# FiltrosRF_R00.net
KiCad netlist of a schematic drawn in Altium Designer
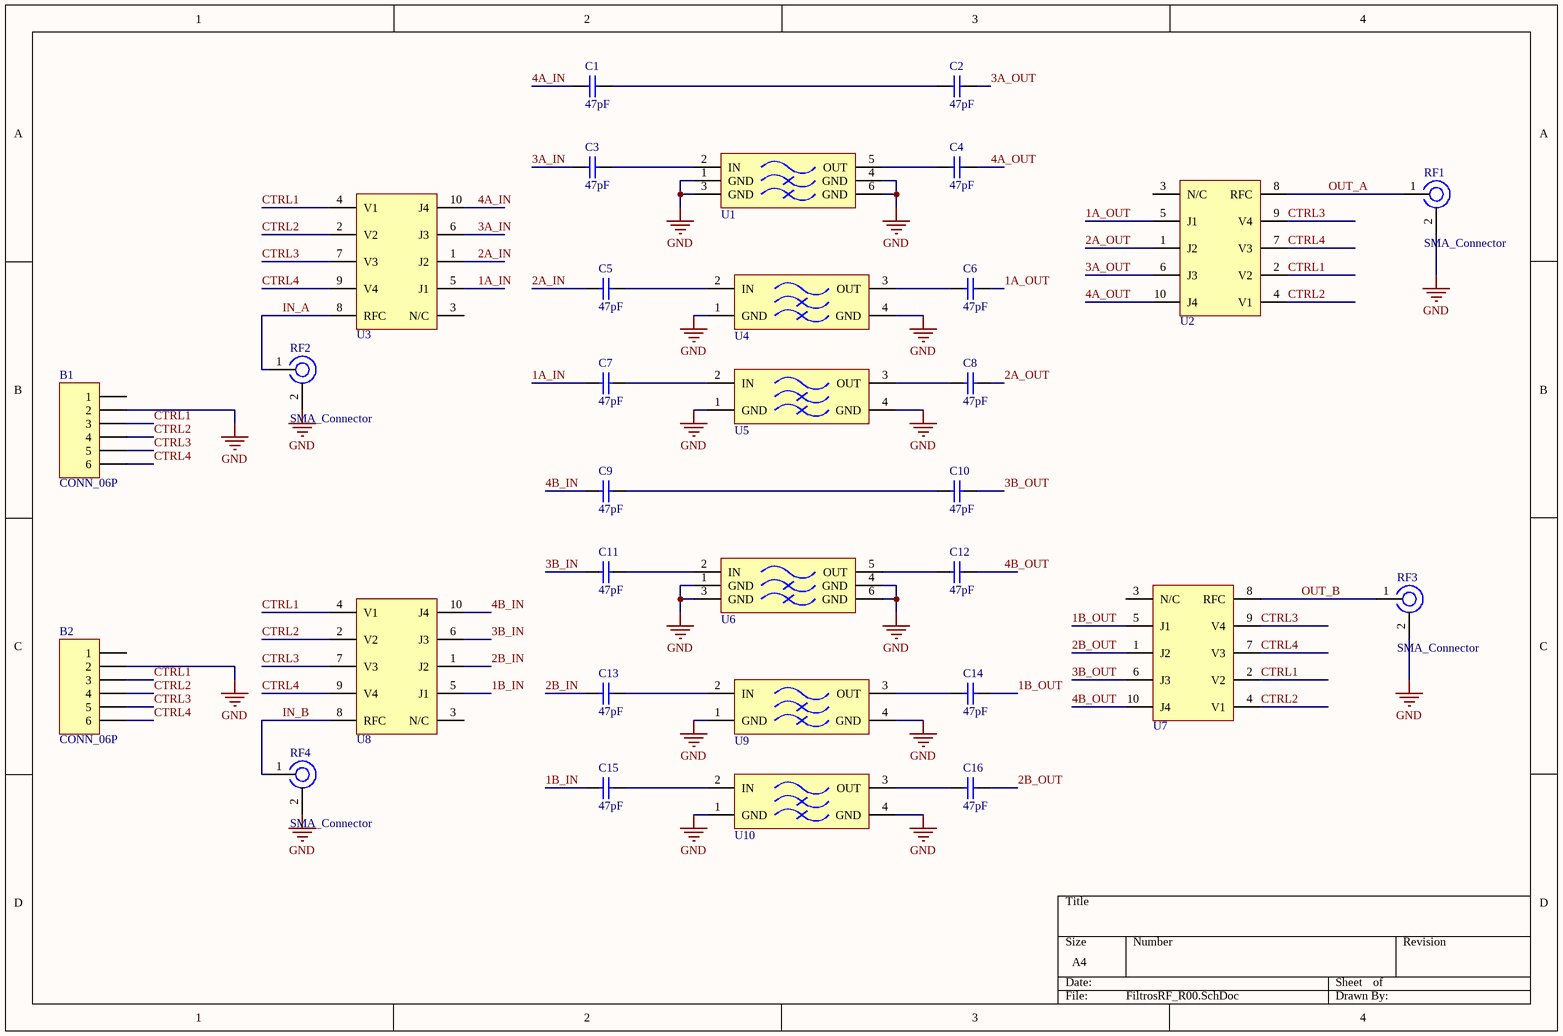
[diagram p0: FiltrosRF_R00.SchDoc]

(export (version "E")
  (design (tool "Eeschema 10.0.6"))
  (components
    (comp (ref "B1")
      (value "CONN_06P")
      (description "Connector Generic 4 Vias")
      (libsource (lib "SchLib_PocketAnalyzer") (part "CONN_06P"))
    )
    (comp (ref "B2")
      (value "CONN_06P")
      (description "Connector Generic 4 Vias")
      (libsource (lib "SchLib_PocketAnalyzer") (part "CONN_06P"))
    )
    (comp (ref "C1")
      (value "47pF")
      (footprint "C_0603")
      (description "Capacitor")
      (libsource (lib "Simulation Generic Components") (part "Capacitor"))
    )
    (comp (ref "C2")
      (value "47pF")
      (footprint "C_0603")
      (description "Capacitor")
      (libsource (lib "Simulation Generic Components") (part "Capacitor"))
    )
    (comp (ref "C3")
      (value "47pF")
      (footprint "C_0603")
      (description "Capacitor")
      (libsource (lib "Simulation Generic Components") (part "Capacitor"))
    )
    (comp (ref "C4")
      (value "47pF")
      (footprint "C_0603")
      (description "Capacitor")
      (libsource (lib "Simulation Generic Components") (part "Capacitor"))
    )
    (comp (ref "C5")
      (value "47pF")
      (footprint "C_0603")
      (description "Capacitor")
      (libsource (lib "Simulation Generic Components") (part "Capacitor"))
    )
    (comp (ref "C6")
      (value "47pF")
      (footprint "C_0603")
      (description "Capacitor")
      (libsource (lib "Simulation Generic Components") (part "Capacitor"))
    )
    (comp (ref "C7")
      (value "47pF")
      (footprint "C_0603")
      (description "Capacitor")
      (libsource (lib "Simulation Generic Components") (part "Capacitor"))
    )
    (comp (ref "C8")
      (value "47pF")
      (footprint "C_0603")
      (description "Capacitor")
      (libsource (lib "Simulation Generic Components") (part "Capacitor"))
    )
    (comp (ref "C9")
      (value "47pF")
      (footprint "C_0603")
      (description "Capacitor")
      (libsource (lib "Simulation Generic Components") (part "Capacitor"))
    )
    (comp (ref "C10")
      (value "47pF")
      (footprint "C_0603")
      (description "Capacitor")
      (libsource (lib "Simulation Generic Components") (part "Capacitor"))
    )
    (comp (ref "C11")
      (value "47pF")
      (footprint "C_0603")
      (description "Capacitor")
      (libsource (lib "Simulation Generic Components") (part "Capacitor"))
    )
    (comp (ref "C12")
      (value "47pF")
      (footprint "C_0603")
      (description "Capacitor")
      (libsource (lib "Simulation Generic Components") (part "Capacitor"))
    )
    (comp (ref "C13")
      (value "47pF")
      (footprint "C_0603")
      (description "Capacitor")
      (libsource (lib "Simulation Generic Components") (part "Capacitor"))
    )
    (comp (ref "C14")
      (value "47pF")
      (footprint "C_0603")
      (description "Capacitor")
      (libsource (lib "Simulation Generic Components") (part "Capacitor"))
    )
    (comp (ref "C15")
      (value "47pF")
      (footprint "C_0603")
      (description "Capacitor")
      (libsource (lib "Simulation Generic Components") (part "Capacitor"))
    )
    (comp (ref "C16")
      (value "47pF")
      (footprint "C_0603")
      (description "Capacitor")
      (libsource (lib "Simulation Generic Components") (part "Capacitor"))
    )
    (comp (ref "RF1")
      (value "SMA_Connector")
      (description "Connector SMA")
      (libsource (lib "SchLib_PocketAnalyzer") (part "SMA_Connector"))
    )
    (comp (ref "RF2")
      (value "SMA_Connector")
      (description "Connector SMA")
      (libsource (lib "SchLib_PocketAnalyzer") (part "SMA_Connector"))
    )
    (comp (ref "RF3")
      (value "SMA_Connector")
      (description "Connector SMA")
      (libsource (lib "SchLib_PocketAnalyzer") (part "SMA_Connector"))
    )
    (comp (ref "RF4")
      (value "SMA_Connector")
      (description "Connector SMA")
      (libsource (lib "SchLib_PocketAnalyzer") (part "SMA_Connector"))
    )
    (comp (ref "U1")
      (value "3550LP14A0300001T")
      (footprint "Low Pass Filter 0603 6 Pins")
      (description "RF FILTER LOW PASS  0603")
      (libsource (lib "FiltrosRF") (part "3550LP14A0300001T"))
    )
    (comp (ref "U2")
      (value "SKY13322-375LF")
      (description "RF Switch IC General Purpose SP4T 6 GHz 50Ohm 10-MLPD (3x2)")
      (libsource (lib "") (part "SKY13322-375LF_1"))
    )
    (comp (ref "U3")
      (value "SKY13322-375LF")
      (description "RF Switch IC General Purpose SP4T 6 GHz 50Ohm 10-MLPD (3x2)")
      (libsource (lib "FiltrosRF") (part "SKY13322-375LF"))
    )
    (comp (ref "U4")
      (value "LP0603A-XXXX-ANTR")
      (footprint "Low Pass Filter 0603 4 Pins")
      (description "RF FILTER 0603")
      (libsource (lib "FiltrosRF") (part "LP0603A-XXXX-ANTR"))
    )
    (comp (ref "U5")
      (value "LP0603A-XXXX-ANTR")
      (footprint "Low Pass Filter 0603 4 Pins")
      (description "RF FILTER 0603")
      (libsource (lib "FiltrosRF") (part "LP0603A-XXXX-ANTR"))
    )
    (comp (ref "U6")
      (value "3550LP14A0300001T")
      (footprint "Low Pass Filter 0603 6 Pins")
      (description "RF FILTER LOW PASS  0603")
      (libsource (lib "FiltrosRF") (part "3550LP14A0300001T"))
    )
    (comp (ref "U7")
      (value "SKY13322-375LF")
      (description "RF Switch IC General Purpose SP4T 6 GHz 50Ohm 10-MLPD (3x2)")
      (libsource (lib "") (part "SKY13322-375LF_1"))
    )
    (comp (ref "U8")
      (value "SKY13322-375LF")
      (description "RF Switch IC General Purpose SP4T 6 GHz 50Ohm 10-MLPD (3x2)")
      (libsource (lib "FiltrosRF") (part "SKY13322-375LF"))
    )
    (comp (ref "U9")
      (value "LP0603A-XXXX-ANTR")
      (footprint "Low Pass Filter 0603 4 Pins")
      (description "RF FILTER 0603")
      (libsource (lib "FiltrosRF") (part "LP0603A-XXXX-ANTR"))
    )
    (comp (ref "U10")
      (value "LP0603A-XXXX-ANTR")
      (footprint "Low Pass Filter 0603 4 Pins")
      (description "RF FILTER 0603")
      (libsource (lib "FiltrosRF") (part "LP0603A-XXXX-ANTR"))
    )
  )
  (nets
    (net (code "1") (name "/1A_IN") (class "Default")
      (node (ref "C7") (pin "1") (pinfunction "1_1") (pintype "passive"))
      (node (ref "U3") (pin "5") (pinfunction "J1_5") (pintype "passive"))
    )
    (net (code "2") (name "/1A_OUT") (class "Default")
      (node (ref "C6") (pin "2") (pinfunction "2_2") (pintype "passive"))
      (node (ref "U2") (pin "5") (pinfunction "J1_5") (pintype "passive"))
    )
    (net (code "3") (name "/1B_IN") (class "Default")
      (node (ref "C15") (pin "1") (pinfunction "1_1") (pintype "passive"))
      (node (ref "U8") (pin "5") (pinfunction "J1_5") (pintype "passive"))
    )
    (net (code "4") (name "/1B_OUT") (class "Default")
      (node (ref "C14") (pin "2") (pinfunction "2_2") (pintype "passive"))
      (node (ref "U7") (pin "5") (pinfunction "J1_5") (pintype "passive"))
    )
    (net (code "5") (name "/2A_IN") (class "Default")
      (node (ref "C5") (pin "1") (pinfunction "1_1") (pintype "passive"))
      (node (ref "U3") (pin "1") (pinfunction "J2_1") (pintype "passive"))
    )
    (net (code "6") (name "/2A_OUT") (class "Default")
      (node (ref "C8") (pin "2") (pinfunction "2_2") (pintype "passive"))
      (node (ref "U2") (pin "1") (pinfunction "J2_1") (pintype "passive"))
    )
    (net (code "7") (name "/2B_IN") (class "Default")
      (node (ref "C13") (pin "1") (pinfunction "1_1") (pintype "passive"))
      (node (ref "U8") (pin "1") (pinfunction "J2_1") (pintype "passive"))
    )
    (net (code "8") (name "/2B_OUT") (class "Default")
      (node (ref "C16") (pin "2") (pinfunction "2_2") (pintype "passive"))
      (node (ref "U7") (pin "1") (pinfunction "J2_1") (pintype "passive"))
    )
    (net (code "9") (name "/3A_IN") (class "Default")
      (node (ref "C3") (pin "1") (pinfunction "1_1") (pintype "passive"))
      (node (ref "U3") (pin "6") (pinfunction "J3_6") (pintype "passive"))
    )
    (net (code "10") (name "/3A_OUT") (class "Default")
      (node (ref "C2") (pin "2") (pinfunction "2_2") (pintype "passive"))
      (node (ref "U2") (pin "6") (pinfunction "J3_6") (pintype "passive"))
    )
    (net (code "11") (name "/3B_IN") (class "Default")
      (node (ref "C11") (pin "1") (pinfunction "1_1") (pintype "passive"))
      (node (ref "U8") (pin "6") (pinfunction "J3_6") (pintype "passive"))
    )
    (net (code "12") (name "/3B_OUT") (class "Default")
      (node (ref "C10") (pin "2") (pinfunction "2_2") (pintype "passive"))
      (node (ref "U7") (pin "6") (pinfunction "J3_6") (pintype "passive"))
    )
    (net (code "13") (name "/4A_IN") (class "Default")
      (node (ref "C1") (pin "1") (pinfunction "1_1") (pintype "passive"))
      (node (ref "U3") (pin "10") (pinfunction "J4_10") (pintype "passive"))
    )
    (net (code "14") (name "/4A_OUT") (class "Default")
      (node (ref "C4") (pin "2") (pinfunction "2_2") (pintype "passive"))
      (node (ref "U2") (pin "10") (pinfunction "J4_10") (pintype "passive"))
    )
    (net (code "15") (name "/4B_IN") (class "Default")
      (node (ref "C9") (pin "1") (pinfunction "1_1") (pintype "passive"))
      (node (ref "U8") (pin "10") (pinfunction "J4_10") (pintype "passive"))
    )
    (net (code "16") (name "/4B_OUT") (class "Default")
      (node (ref "C12") (pin "2") (pinfunction "2_2") (pintype "passive"))
      (node (ref "U7") (pin "10") (pinfunction "J4_10") (pintype "passive"))
    )
    (net (code "17") (name "/CTRL1") (class "Default")
      (node (ref "B1") (pin "3") (pinfunction "3_3") (pintype "passive"))
      (node (ref "B2") (pin "3") (pinfunction "3_3") (pintype "passive"))
      (node (ref "U2") (pin "2") (pinfunction "V2_2") (pintype "passive"))
      (node (ref "U3") (pin "4") (pinfunction "V1_4") (pintype "passive"))
      (node (ref "U7") (pin "2") (pinfunction "V2_2") (pintype "passive"))
      (node (ref "U8") (pin "4") (pinfunction "V1_4") (pintype "passive"))
    )
    (net (code "18") (name "/CTRL2") (class "Default")
      (node (ref "B1") (pin "4") (pinfunction "4_4") (pintype "passive"))
      (node (ref "B2") (pin "4") (pinfunction "4_4") (pintype "passive"))
      (node (ref "U2") (pin "4") (pinfunction "V1_4") (pintype "passive"))
      (node (ref "U3") (pin "2") (pinfunction "V2_2") (pintype "passive"))
      (node (ref "U7") (pin "4") (pinfunction "V1_4") (pintype "passive"))
      (node (ref "U8") (pin "2") (pinfunction "V2_2") (pintype "passive"))
    )
    (net (code "19") (name "/CTRL3") (class "Default")
      (node (ref "B1") (pin "5") (pinfunction "5_5") (pintype "passive"))
      (node (ref "B2") (pin "5") (pinfunction "5_5") (pintype "passive"))
      (node (ref "U2") (pin "9") (pinfunction "V4_9") (pintype "passive"))
      (node (ref "U3") (pin "7") (pinfunction "V3_7") (pintype "passive"))
      (node (ref "U7") (pin "9") (pinfunction "V4_9") (pintype "passive"))
      (node (ref "U8") (pin "7") (pinfunction "V3_7") (pintype "passive"))
    )
    (net (code "20") (name "/CTRL4") (class "Default")
      (node (ref "B1") (pin "6") (pinfunction "6_6") (pintype "passive"))
      (node (ref "B2") (pin "6") (pinfunction "6_6") (pintype "passive"))
      (node (ref "U2") (pin "7") (pinfunction "V3_7") (pintype "passive"))
      (node (ref "U3") (pin "9") (pinfunction "V4_9") (pintype "passive"))
      (node (ref "U7") (pin "7") (pinfunction "V3_7") (pintype "passive"))
      (node (ref "U8") (pin "9") (pinfunction "V4_9") (pintype "passive"))
    )
    (net (code "21") (name "/IN_A") (class "Default")
      (node (ref "RF2") (pin "1") (pinfunction "1_1") (pintype "passive"))
      (node (ref "U3") (pin "8") (pinfunction "RFC_8") (pintype "passive"))
    )
    (net (code "22") (name "/IN_B") (class "Default")
      (node (ref "RF4") (pin "1") (pinfunction "1_1") (pintype "passive"))
      (node (ref "U8") (pin "8") (pinfunction "RFC_8") (pintype "passive"))
    )
    (net (code "23") (name "/OUT_A") (class "Default")
      (node (ref "RF1") (pin "1") (pinfunction "1_1") (pintype "passive"))
      (node (ref "U2") (pin "8") (pinfunction "RFC_8") (pintype "passive"))
    )
    (net (code "24") (name "/OUT_B") (class "Default")
      (node (ref "RF3") (pin "1") (pinfunction "1_1") (pintype "passive"))
      (node (ref "U7") (pin "8") (pinfunction "RFC_8") (pintype "passive"))
    )
    (net (code "25") (name "GND") (class "Default")
      (node (ref "B1") (pin "2") (pinfunction "2_2") (pintype "passive"))
      (node (ref "B2") (pin "2") (pinfunction "2_2") (pintype "passive"))
      (node (ref "RF1") (pin "2") (pinfunction "2_2") (pintype "passive"))
      (node (ref "RF2") (pin "2") (pinfunction "2_2") (pintype "passive"))
      (node (ref "RF3") (pin "2") (pinfunction "2_2") (pintype "passive"))
      (node (ref "RF4") (pin "2") (pinfunction "2_2") (pintype "passive"))
      (node (ref "U1") (pin "1") (pinfunction "GND_1") (pintype "passive"))
      (node (ref "U1") (pin "3") (pinfunction "GND_3") (pintype "passive"))
      (node (ref "U1") (pin "4") (pinfunction "GND_4") (pintype "passive"))
      (node (ref "U1") (pin "6") (pinfunction "GND_6") (pintype "passive"))
      (node (ref "U10") (pin "1") (pinfunction "GND_1") (pintype "passive"))
      (node (ref "U10") (pin "4") (pinfunction "GND_4") (pintype "passive"))
      (node (ref "U4") (pin "1") (pinfunction "GND_1") (pintype "passive"))
      (node (ref "U4") (pin "4") (pinfunction "GND_4") (pintype "passive"))
      (node (ref "U5") (pin "1") (pinfunction "GND_1") (pintype "passive"))
      (node (ref "U5") (pin "4") (pinfunction "GND_4") (pintype "passive"))
      (node (ref "U6") (pin "1") (pinfunction "GND_1") (pintype "passive"))
      (node (ref "U6") (pin "3") (pinfunction "GND_3") (pintype "passive"))
      (node (ref "U6") (pin "4") (pinfunction "GND_4") (pintype "passive"))
      (node (ref "U6") (pin "6") (pinfunction "GND_6") (pintype "passive"))
      (node (ref "U9") (pin "1") (pinfunction "GND_1") (pintype "passive"))
      (node (ref "U9") (pin "4") (pinfunction "GND_4") (pintype "passive"))
    )
    (net (code "26") (name "Net-(C1-Pad2)") (class "Default")
      (node (ref "C1") (pin "2") (pinfunction "2_2") (pintype "passive"))
      (node (ref "C2") (pin "1") (pinfunction "1_1") (pintype "passive"))
    )
    (net (code "27") (name "Net-(C10-Pad1)") (class "Default")
      (node (ref "C10") (pin "1") (pinfunction "1_1") (pintype "passive"))
      (node (ref "C9") (pin "2") (pinfunction "2_2") (pintype "passive"))
    )
    (net (code "28") (name "Net-(U1-IN)") (class "Default")
      (node (ref "C3") (pin "2") (pinfunction "2_2") (pintype "passive"))
      (node (ref "U1") (pin "2") (pinfunction "IN_2") (pintype "passive"))
    )
    (net (code "29") (name "Net-(U1-OUT)") (class "Default")
      (node (ref "C4") (pin "1") (pinfunction "1_1") (pintype "passive"))
      (node (ref "U1") (pin "5") (pinfunction "OUT_5") (pintype "passive"))
    )
    (net (code "30") (name "Net-(U4-IN)") (class "Default")
      (node (ref "C5") (pin "2") (pinfunction "2_2") (pintype "passive"))
      (node (ref "U4") (pin "2") (pinfunction "IN_2") (pintype "passive"))
    )
    (net (code "31") (name "Net-(U4-OUT)") (class "Default")
      (node (ref "C6") (pin "1") (pinfunction "1_1") (pintype "passive"))
      (node (ref "U4") (pin "3") (pinfunction "OUT_3") (pintype "passive"))
    )
    (net (code "32") (name "Net-(U5-IN)") (class "Default")
      (node (ref "C7") (pin "2") (pinfunction "2_2") (pintype "passive"))
      (node (ref "U5") (pin "2") (pinfunction "IN_2") (pintype "passive"))
    )
    (net (code "33") (name "Net-(U5-OUT)") (class "Default")
      (node (ref "C8") (pin "1") (pinfunction "1_1") (pintype "passive"))
      (node (ref "U5") (pin "3") (pinfunction "OUT_3") (pintype "passive"))
    )
    (net (code "34") (name "Net-(U6-IN)") (class "Default")
      (node (ref "C11") (pin "2") (pinfunction "2_2") (pintype "passive"))
      (node (ref "U6") (pin "2") (pinfunction "IN_2") (pintype "passive"))
    )
    (net (code "35") (name "Net-(U6-OUT)") (class "Default")
      (node (ref "C12") (pin "1") (pinfunction "1_1") (pintype "passive"))
      (node (ref "U6") (pin "5") (pinfunction "OUT_5") (pintype "passive"))
    )
    (net (code "36") (name "Net-(U9-IN)") (class "Default")
      (node (ref "C13") (pin "2") (pinfunction "2_2") (pintype "passive"))
      (node (ref "U9") (pin "2") (pinfunction "IN_2") (pintype "passive"))
    )
    (net (code "37") (name "Net-(U9-OUT)") (class "Default")
      (node (ref "C14") (pin "1") (pinfunction "1_1") (pintype "passive"))
      (node (ref "U9") (pin "3") (pinfunction "OUT_3") (pintype "passive"))
    )
    (net (code "38") (name "Net-(U10-IN)") (class "Default")
      (node (ref "C15") (pin "2") (pinfunction "2_2") (pintype "passive"))
      (node (ref "U10") (pin "2") (pinfunction "IN_2") (pintype "passive"))
    )
    (net (code "39") (name "Net-(U10-OUT)") (class "Default")
      (node (ref "C16") (pin "1") (pinfunction "1_1") (pintype "passive"))
      (node (ref "U10") (pin "3") (pinfunction "OUT_3") (pintype "passive"))
    )
    (net (code "40") (name "unconnected-(B1-Pad1)") (class "Default")
      (node (ref "B1") (pin "1") (pinfunction "1_1") (pintype "passive"))
    )
    (net (code "41") (name "unconnected-(B2-Pad1)") (class "Default")
      (node (ref "B2") (pin "1") (pinfunction "1_1") (pintype "passive"))
    )
    (net (code "42") (name "unconnected-(U2-N{slash}C-Pad3)") (class "Default")
      (node (ref "U2") (pin "3") (pinfunction "N/C_3") (pintype "passive"))
    )
    (net (code "43") (name "unconnected-(U3-N{slash}C-Pad3)") (class "Default")
      (node (ref "U3") (pin "3") (pinfunction "N/C_3") (pintype "passive"))
    )
    (net (code "44") (name "unconnected-(U7-N{slash}C-Pad3)") (class "Default")
      (node (ref "U7") (pin "3") (pinfunction "N/C_3") (pintype "passive"))
    )
    (net (code "45") (name "unconnected-(U8-N{slash}C-Pad3)") (class "Default")
      (node (ref "U8") (pin "3") (pinfunction "N/C_3") (pintype "passive"))
    )
  )
)
